# v1.net
KiCad netlist of a schematic drawn in EAGLE
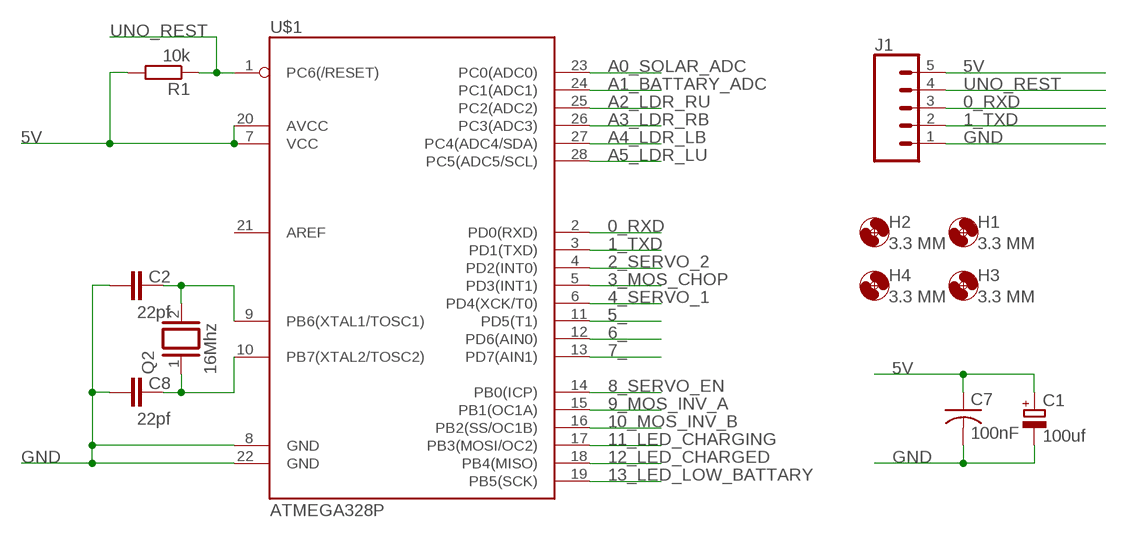
[diagram p0: schematic, sheet 1]
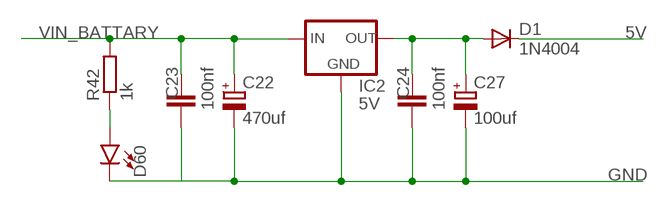
[diagram p1: schematic, sheet 2]
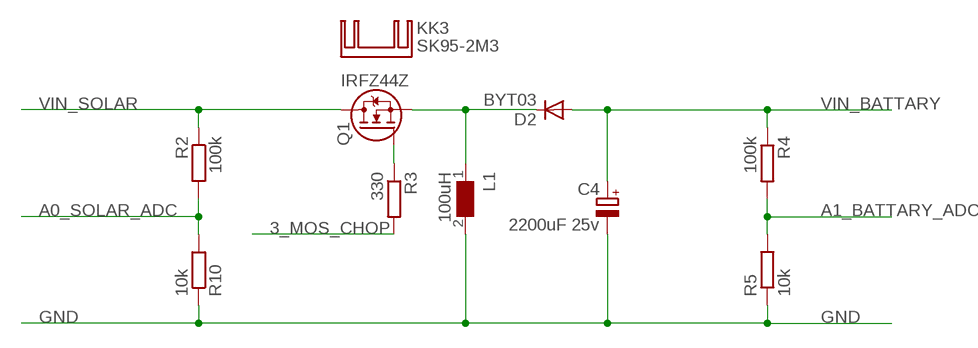
[diagram p2: schematic, sheet 3]
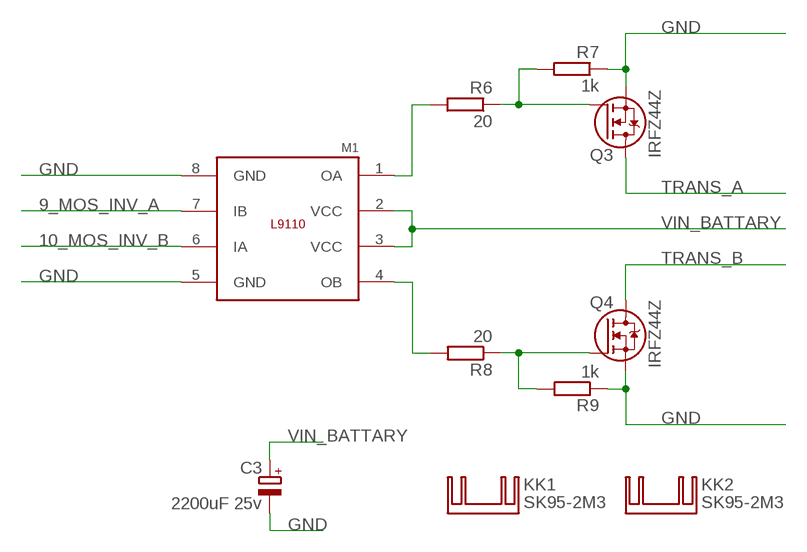
[diagram p3: schematic, sheet 4]
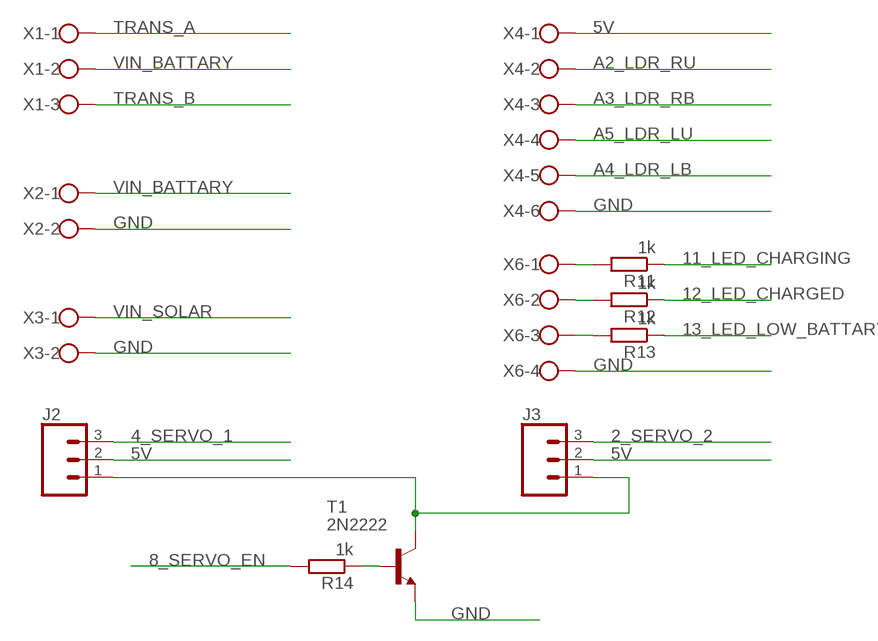
[diagram p4: schematic, sheet 5]

(export (version "E")
  (design (tool "Eeschema 10.0.6"))
  (components
    (comp (ref "C3")
      (value "2200uF 25v")
      (footprint "eagle-import:E5-13")
      (libsource (lib "eagle-import") (part "rcl_334_CPOL-EUE5-13"))
    )
    (comp (ref "KK1")
      (value "SK95-2M3")
      (footprint "eagle-import:SK95-2M3")
      (libsource (lib "eagle-import") (part "SK95-2M3"))
    )
    (comp (ref "KK2")
      (value "SK95-2M3")
      (footprint "eagle-import:SK95-2M3")
      (libsource (lib "eagle-import") (part "SK95-2M3"))
    )
    (comp (ref "M1")
      (value "L9110")
      (footprint "eagle-import:SO8P")
      (libsource (lib "eagle-import") (part "L9110"))
    )
    (comp (ref "Q3")
      (value "IRFZ44Z")
      (footprint "eagle-import:TO220V")
      (libsource (lib "eagle-import") (part "IRFZ44Z"))
    )
    (comp (ref "Q4")
      (value "IRFZ44Z")
      (footprint "eagle-import:TO220V")
      (libsource (lib "eagle-import") (part "IRFZ44Z"))
    )
    (comp (ref "R6")
      (value "20")
      (footprint "eagle-import:0207_10")
      (libsource (lib "eagle-import") (part "R-EU_0207/10"))
    )
    (comp (ref "R7")
      (value "1k")
      (footprint "eagle-import:0207_10")
      (libsource (lib "eagle-import") (part "R-EU_0207/10"))
    )
    (comp (ref "R8")
      (value "20")
      (footprint "eagle-import:0207_10")
      (libsource (lib "eagle-import") (part "R-EU_0207/10"))
    )
    (comp (ref "R9")
      (value "1k")
      (footprint "eagle-import:0207_10")
      (libsource (lib "eagle-import") (part "R-EU_0207/10"))
    )
    (comp (ref "C4")
      (value "2200uF 25v")
      (footprint "eagle-import:E5-13")
      (libsource (lib "eagle-import") (part "rcl_334_CPOL-EUE5-13"))
    )
    (comp (ref "D2")
      (value "BYT03")
      (footprint "eagle-import:DO27-15")
      (libsource (lib "eagle-import") (part "BYT03"))
    )
    (comp (ref "KK3")
      (value "SK95-2M3")
      (footprint "eagle-import:SK95-2M3")
      (libsource (lib "eagle-import") (part "SK95-2M3"))
    )
    (comp (ref "L1")
      (value "100uH")
      (footprint "eagle-import:WE-ZB")
      (libsource (lib "eagle-import") (part "WE-ZB"))
    )
    (comp (ref "Q1")
      (value "IRFZ44Z")
      (footprint "eagle-import:TO220V")
      (libsource (lib "eagle-import") (part "IRFZ44Z"))
    )
    (comp (ref "R2")
      (value "100k")
      (footprint "eagle-import:0207_10")
      (libsource (lib "eagle-import") (part "R-EU_0207/10"))
    )
    (comp (ref "R3")
      (value "330")
      (footprint "eagle-import:0207_10")
      (libsource (lib "eagle-import") (part "R-EU_0207/10"))
    )
    (comp (ref "R4")
      (value "100k")
      (footprint "eagle-import:0207_10")
      (libsource (lib "eagle-import") (part "R-EU_0207/10"))
    )
    (comp (ref "R5")
      (value "10k")
      (footprint "eagle-import:0207_10")
      (libsource (lib "eagle-import") (part "R-EU_0207/10"))
    )
    (comp (ref "R10")
      (value "10k")
      (footprint "eagle-import:0207_10")
      (libsource (lib "eagle-import") (part "R-EU_0207/10"))
    )
    (comp (ref "C22")
      (value "470uf")
      (footprint "eagle-import:E3,5-8")
      (libsource (lib "eagle-import") (part "CPOL-EUE3.5-8"))
    )
    (comp (ref "C23")
      (value "100nf")
      (footprint "eagle-import:C050-030X075")
      (libsource (lib "eagle-import") (part "C-EU050-030X075"))
    )
    (comp (ref "C24")
      (value "100nf")
      (footprint "eagle-import:C050-030X075")
      (libsource (lib "eagle-import") (part "C-EU050-030X075"))
    )
    (comp (ref "C27")
      (value "100uf")
      (footprint "eagle-import:E3,5-8")
      (libsource (lib "eagle-import") (part "CPOL-EUE3.5-8"))
    )
    (comp (ref "D1")
      (value "1N4004")
      (footprint "eagle-import:DO41-10")
      (libsource (lib "eagle-import") (part "1N4004"))
    )
    (comp (ref "D60")
      (value "LED5MM")
      (footprint "eagle-import:LED_5MM")
      (libsource (lib "eagle-import") (part "LED5MM"))
    )
    (comp (ref "IC2")
      (value "5V")
      (footprint "eagle-import:78XXL")
      (libsource (lib "eagle-import") (part "V_REG_78XXSIDE"))
    )
    (comp (ref "R42")
      (value "1k")
      (footprint "eagle-import:0207_10")
      (libsource (lib "eagle-import") (part "R-EU_0207/10"))
    )
    (comp (ref "J2")
      (value "CONN_03JST-PTH-VERT")
      (footprint "eagle-import:JST-3-PTH-VERT")
      (libsource (lib "eagle-import") (part "CONN_03JST-PTH-VERT"))
    )
    (comp (ref "J3")
      (value "CONN_03JST-PTH-VERT")
      (footprint "eagle-import:JST-3-PTH-VERT")
      (libsource (lib "eagle-import") (part "CONN_03JST-PTH-VERT"))
    )
    (comp (ref "R11")
      (value "1k")
      (footprint "eagle-import:0207_10")
      (libsource (lib "eagle-import") (part "R-EU_0207/10"))
    )
    (comp (ref "R12")
      (value "1k")
      (footprint "eagle-import:0207_10")
      (libsource (lib "eagle-import") (part "R-EU_0207/10"))
    )
    (comp (ref "R13")
      (value "1k")
      (footprint "eagle-import:0207_10")
      (libsource (lib "eagle-import") (part "R-EU_0207/10"))
    )
    (comp (ref "R14")
      (value "1k")
      (footprint "eagle-import:0207_10")
      (libsource (lib "eagle-import") (part "R-EU_0207/10"))
    )
    (comp (ref "T1")
      (value "2N2222")
      (footprint "eagle-import:TO92-EBC-OVAL")
      (libsource (lib "eagle-import") (part "2N2222"))
    )
    (comp (ref "X1")
      (value "W237-103")
      (footprint "eagle-import:W237-103")
      (fields (field (name "MPN") "237-103"))
      (libsource (lib "eagle-import") (part "W237-103"))
    )
    (comp (ref "X2")
      (value "W237-102")
      (footprint "eagle-import:W237-102")
      (fields (field (name "MPN") "237-102"))
      (libsource (lib "eagle-import") (part "W237-102"))
    )
    (comp (ref "X3")
      (value "W237-102")
      (footprint "eagle-import:W237-102")
      (fields (field (name "MPN") "237-102"))
      (libsource (lib "eagle-import") (part "W237-102"))
    )
    (comp (ref "X4")
      (value "W237-6")
      (footprint "eagle-import:W237-6")
      (libsource (lib "eagle-import") (part "W237-6"))
    )
    (comp (ref "X6")
      (value "W237-4")
      (footprint "eagle-import:W237-4")
      (libsource (lib "eagle-import") (part "W237-4"))
    )
    (comp (ref "C1")
      (value "100uf")
      (footprint "eagle-import:E3,5-8")
      (libsource (lib "eagle-import") (part "CPOL-EUE3.5-8"))
    )
    (comp (ref "C2")
      (value "22pf")
      (footprint "eagle-import:C050-030X075")
      (libsource (lib "eagle-import") (part "C-EU050-030X075"))
    )
    (comp (ref "C7")
      (value "100nF")
      (footprint "eagle-import:C050-035X075")
      (libsource (lib "eagle-import") (part "C-US050-035X075"))
    )
    (comp (ref "C8")
      (value "22pf")
      (footprint "eagle-import:C050-030X075")
      (libsource (lib "eagle-import") (part "C-EU050-030X075"))
    )
    (comp (ref "H1")
      (value "3.3 MM")
      (footprint "eagle-import:3,3")
      (libsource (lib "eagle-import") (part "MOUNT-HOLE3.3"))
    )
    (comp (ref "H2")
      (value "3.3 MM")
      (footprint "eagle-import:3,3")
      (libsource (lib "eagle-import") (part "MOUNT-HOLE3.3"))
    )
    (comp (ref "H3")
      (value "3.3 MM")
      (footprint "eagle-import:3,3")
      (libsource (lib "eagle-import") (part "MOUNT-HOLE3.3"))
    )
    (comp (ref "H4")
      (value "3.3 MM")
      (footprint "eagle-import:3,3")
      (libsource (lib "eagle-import") (part "MOUNT-HOLE3.3"))
    )
    (comp (ref "J1")
      (value "CONN_05JST-VERT")
      (footprint "eagle-import:JST-5-PTH-VERT")
      (libsource (lib "eagle-import") (part "CONN_05JST-VERT"))
    )
    (comp (ref "Q2")
      (value "16Mhz")
      (footprint "eagle-import:QS")
      (libsource (lib "eagle-import") (part "XTAL/S"))
    )
    (comp (ref "R1")
      (value "10k")
      (footprint "eagle-import:0207_10")
      (libsource (lib "eagle-import") (part "R-EU_0207/10"))
    )
    (comp (ref "U$1")
      (value "ATMEGA328P")
      (footprint "eagle-import:DIL-28-3")
      (libsource (lib "eagle-import") (part "ATMEGA328P_PDIP"))
    )
  )
  (nets
    (net (code "1") (name "0_RXD") (class "Default")
      (node (ref "J1") (pin "3") (pinfunction "3_3") (pintype "passive"))
      (node (ref "U$1") (pin "2") (pinfunction "PD0(RXD)_2") (pintype "bidirectional"))
    )
    (net (code "2") (name "1_TXD") (class "Default")
      (node (ref "J1") (pin "2") (pinfunction "2_2") (pintype "passive"))
      (node (ref "U$1") (pin "3") (pinfunction "PD1(TXD)_3") (pintype "bidirectional"))
    )
    (net (code "3") (name "2_SERVO_2") (class "Default")
      (node (ref "J3") (pin "3") (pinfunction "3_3") (pintype "passive"))
      (node (ref "U$1") (pin "4") (pinfunction "PD2(INT0)_4") (pintype "bidirectional"))
    )
    (net (code "4") (name "3_MOS_CHOP") (class "Default")
      (node (ref "R3") (pin "2") (pinfunction "2_2") (pintype "passive"))
      (node (ref "U$1") (pin "5") (pinfunction "PD3(INT1)_5") (pintype "bidirectional"))
    )
    (net (code "5") (name "4_SERVO_1") (class "Default")
      (node (ref "J2") (pin "3") (pinfunction "3_3") (pintype "passive"))
      (node (ref "U$1") (pin "6") (pinfunction "PD4(XCK/T0)_6") (pintype "bidirectional"))
    )
    (net (code "6") (name "5V") (class "Default")
      (node (ref "C1") (pin "+") (pinfunction "+_+") (pintype "passive"))
      (node (ref "C7") (pin "1") (pinfunction "1_1") (pintype "passive"))
      (node (ref "D1") (pin "C") (pinfunction "C_C") (pintype "passive"))
      (node (ref "J1") (pin "5") (pinfunction "5_5") (pintype "passive"))
      (node (ref "J2") (pin "2") (pinfunction "2_2") (pintype "passive"))
      (node (ref "J3") (pin "2") (pinfunction "2_2") (pintype "passive"))
      (node (ref "R1") (pin "2") (pinfunction "2_2") (pintype "passive"))
      (node (ref "U$1") (pin "20") (pinfunction "AVCC_20") (pintype "bidirectional"))
      (node (ref "U$1") (pin "7") (pinfunction "VCC_7") (pintype "bidirectional"))
      (node (ref "X4") (pin "1") (pinfunction "KL_1") (pintype "passive"))
    )
    (net (code "7") (name "5_") (class "Default")
      (node (ref "U$1") (pin "11") (pinfunction "PD5(T1)_11") (pintype "bidirectional"))
    )
    (net (code "8") (name "6_") (class "Default")
      (node (ref "U$1") (pin "12") (pinfunction "PD6(AIN0)_12") (pintype "bidirectional"))
    )
    (net (code "9") (name "7_") (class "Default")
      (node (ref "U$1") (pin "13") (pinfunction "PD7(AIN1)_13") (pintype "bidirectional"))
    )
    (net (code "10") (name "8_SERVO_EN") (class "Default")
      (node (ref "R14") (pin "2") (pinfunction "2_2") (pintype "passive"))
      (node (ref "U$1") (pin "14") (pinfunction "PB0(ICP)_14") (pintype "bidirectional"))
    )
    (net (code "11") (name "9_MOS_INV_A") (class "Default")
      (node (ref "M1") (pin "7") (pinfunction "IB_7") (pintype "bidirectional"))
      (node (ref "U$1") (pin "15") (pinfunction "PB1(OC1A)_15") (pintype "bidirectional"))
    )
    (net (code "12") (name "10_MOS_INV_B") (class "Default")
      (node (ref "M1") (pin "6") (pinfunction "IA_6") (pintype "bidirectional"))
      (node (ref "U$1") (pin "16") (pinfunction "PB2(SS/OC1B)_16") (pintype "bidirectional"))
    )
    (net (code "13") (name "11_LED_CHARGING") (class "Default")
      (node (ref "R11") (pin "1") (pinfunction "1_1") (pintype "passive"))
      (node (ref "U$1") (pin "17") (pinfunction "PB3(MOSI/OC2)_17") (pintype "bidirectional"))
    )
    (net (code "14") (name "12_LED_CHARGED") (class "Default")
      (node (ref "R12") (pin "1") (pinfunction "1_1") (pintype "passive"))
      (node (ref "U$1") (pin "18") (pinfunction "PB4(MISO)_18") (pintype "bidirectional"))
    )
    (net (code "15") (name "13_LED_LOW_BATTARY") (class "Default")
      (node (ref "R13") (pin "1") (pinfunction "1_1") (pintype "passive"))
      (node (ref "U$1") (pin "19") (pinfunction "PB5(SCK)_19") (pintype "bidirectional"))
    )
    (net (code "16") (name "A0_SOLAR_ADC") (class "Default")
      (node (ref "R10") (pin "2") (pinfunction "2_2") (pintype "passive"))
      (node (ref "R2") (pin "2") (pinfunction "2_2") (pintype "passive"))
      (node (ref "U$1") (pin "23") (pinfunction "PC0(ADC0)_23") (pintype "bidirectional"))
    )
    (net (code "17") (name "A1_BATTARY_ADC") (class "Default")
      (node (ref "R4") (pin "2") (pinfunction "2_2") (pintype "passive"))
      (node (ref "R5") (pin "2") (pinfunction "2_2") (pintype "passive"))
      (node (ref "U$1") (pin "24") (pinfunction "PC1(ADC1)_24") (pintype "bidirectional"))
    )
    (net (code "18") (name "A2_LDR_RU") (class "Default")
      (node (ref "U$1") (pin "25") (pinfunction "PC2(ADC2)_25") (pintype "bidirectional"))
      (node (ref "X4") (pin "2") (pinfunction "KL_2") (pintype "passive"))
    )
    (net (code "19") (name "A3_LDR_RB") (class "Default")
      (node (ref "U$1") (pin "26") (pinfunction "PC3(ADC3)_26") (pintype "bidirectional"))
      (node (ref "X4") (pin "3") (pinfunction "KL_3") (pintype "passive"))
    )
    (net (code "20") (name "A4_LDR_LB") (class "Default")
      (node (ref "U$1") (pin "27") (pinfunction "PC4(ADC4/SDA)_27") (pintype "bidirectional"))
      (node (ref "X4") (pin "5") (pinfunction "KL_5") (pintype "passive"))
    )
    (net (code "21") (name "A5_LDR_LU") (class "Default")
      (node (ref "U$1") (pin "28") (pinfunction "PC5(ADC5/SCL)_28") (pintype "bidirectional"))
      (node (ref "X4") (pin "4") (pinfunction "KL_4") (pintype "passive"))
    )
    (net (code "22") (name "GND") (class "Default")
      (node (ref "C1") (pin "-") (pinfunction "-_-") (pintype "passive"))
      (node (ref "C2") (pin "1") (pinfunction "1_1") (pintype "passive"))
      (node (ref "C22") (pin "-") (pinfunction "-_-") (pintype "passive"))
      (node (ref "C23") (pin "1") (pinfunction "1_1") (pintype "passive"))
      (node (ref "C24") (pin "1") (pinfunction "1_1") (pintype "passive"))
      (node (ref "C27") (pin "-") (pinfunction "-_-") (pintype "passive"))
      (node (ref "C3") (pin "-") (pinfunction "-_-") (pintype "passive"))
      (node (ref "C4") (pin "-") (pinfunction "-_-") (pintype "passive"))
      (node (ref "C7") (pin "2") (pinfunction "2_2") (pintype "passive"))
      (node (ref "C8") (pin "1") (pinfunction "1_1") (pintype "passive"))
      (node (ref "D60") (pin "K") (pinfunction "C_K") (pintype "passive"))
      (node (ref "IC2") (pin "GND") (pinfunction "GND_GND") (pintype "input"))
      (node (ref "J1") (pin "1") (pinfunction "1_1") (pintype "passive"))
      (node (ref "L1") (pin "2") (pinfunction "2_2") (pintype "passive"))
      (node (ref "M1") (pin "5") (pinfunction "GND_5") (pintype "bidirectional"))
      (node (ref "M1") (pin "8") (pinfunction "GND_8") (pintype "bidirectional"))
      (node (ref "Q3") (pin "3") (pinfunction "S_3") (pintype "passive"))
      (node (ref "Q4") (pin "3") (pinfunction "S_3") (pintype "passive"))
      (node (ref "R10") (pin "1") (pinfunction "1_1") (pintype "passive"))
      (node (ref "R5") (pin "1") (pinfunction "1_1") (pintype "passive"))
      (node (ref "R7") (pin "1") (pinfunction "1_1") (pintype "passive"))
      (node (ref "R9") (pin "1") (pinfunction "1_1") (pintype "passive"))
      (node (ref "T1") (pin "E") (pinfunction "E_E") (pintype "passive"))
      (node (ref "U$1") (pin "22") (pinfunction "GND_22") (pintype "bidirectional"))
      (node (ref "U$1") (pin "8") (pinfunction "GND_8") (pintype "bidirectional"))
      (node (ref "X2") (pin "2") (pinfunction "KL_2") (pintype "passive"))
      (node (ref "X3") (pin "2") (pinfunction "KL_2") (pintype "passive"))
      (node (ref "X4") (pin "6") (pinfunction "KL_6") (pintype "passive"))
      (node (ref "X6") (pin "4") (pinfunction "KL_4") (pintype "passive"))
    )
    (net (code "23") (name "Net-(C24-Pad2)") (class "Default")
      (node (ref "C24") (pin "2") (pinfunction "2_2") (pintype "passive"))
      (node (ref "C27") (pin "+") (pinfunction "+_+") (pintype "passive"))
      (node (ref "D1") (pin "A") (pinfunction "A_A") (pintype "passive"))
      (node (ref "IC2") (pin "OUT") (pinfunction "OUT_OUT") (pintype "output"))
    )
    (net (code "24") (name "Net-(D60-PadA)") (class "Default")
      (node (ref "D60") (pin "A") (pinfunction "A_A") (pintype "passive"))
      (node (ref "R42") (pin "1") (pinfunction "1_1") (pintype "passive"))
    )
    (net (code "25") (name "Net-(J2-Pad1)") (class "Default")
      (node (ref "J2") (pin "1") (pinfunction "1_1") (pintype "passive"))
      (node (ref "J3") (pin "1") (pinfunction "1_1") (pintype "passive"))
      (node (ref "T1") (pin "C") (pinfunction "C_C") (pintype "passive"))
    )
    (net (code "26") (name "Net-(M1-OA)") (class "Default")
      (node (ref "M1") (pin "1") (pinfunction "OA_1") (pintype "bidirectional"))
      (node (ref "R6") (pin "2") (pinfunction "2_2") (pintype "passive"))
    )
    (net (code "27") (name "Net-(M1-OB)") (class "Default")
      (node (ref "M1") (pin "4") (pinfunction "OB_4") (pintype "bidirectional"))
      (node (ref "R8") (pin "2") (pinfunction "2_2") (pintype "passive"))
    )
    (net (code "28") (name "Net-(Q1-G)") (class "Default")
      (node (ref "Q1") (pin "1") (pinfunction "G_1") (pintype "passive"))
      (node (ref "R3") (pin "1") (pinfunction "1_1") (pintype "passive"))
    )
    (net (code "29") (name "Net-(Q1-S)") (class "Default")
      (node (ref "D2") (pin "C") (pinfunction "C_C") (pintype "passive"))
      (node (ref "L1") (pin "1") (pinfunction "1_1") (pintype "passive"))
      (node (ref "Q1") (pin "3") (pinfunction "S_3") (pintype "passive"))
    )
    (net (code "30") (name "Net-(Q3-G)") (class "Default")
      (node (ref "Q3") (pin "1") (pinfunction "G_1") (pintype "passive"))
      (node (ref "R6") (pin "1") (pinfunction "1_1") (pintype "passive"))
      (node (ref "R7") (pin "2") (pinfunction "2_2") (pintype "passive"))
    )
    (net (code "31") (name "Net-(Q4-G)") (class "Default")
      (node (ref "Q4") (pin "1") (pinfunction "G_1") (pintype "passive"))
      (node (ref "R8") (pin "1") (pinfunction "1_1") (pintype "passive"))
      (node (ref "R9") (pin "2") (pinfunction "2_2") (pintype "passive"))
    )
    (net (code "32") (name "Net-(R14-Pad1)") (class "Default")
      (node (ref "R14") (pin "1") (pinfunction "1_1") (pintype "passive"))
      (node (ref "T1") (pin "B") (pinfunction "B_B") (pintype "passive"))
    )
    (net (code "33") (name "Net-(U$1-PB6(XTAL1{slash}TOSC1))") (class "Default")
      (node (ref "C2") (pin "2") (pinfunction "2_2") (pintype "passive"))
      (node (ref "Q2") (pin "2") (pinfunction "2_2") (pintype "passive"))
      (node (ref "U$1") (pin "9") (pinfunction "PB6(XTAL1/TOSC1)_9") (pintype "bidirectional"))
    )
    (net (code "34") (name "Net-(U$1-PB7(XTAL2{slash}TOSC2))") (class "Default")
      (node (ref "C8") (pin "2") (pinfunction "2_2") (pintype "passive"))
      (node (ref "Q2") (pin "1") (pinfunction "1_1") (pintype "passive"))
      (node (ref "U$1") (pin "10") (pinfunction "PB7(XTAL2/TOSC2)_10") (pintype "bidirectional"))
    )
    (net (code "35") (name "Net-(X6A-KL)") (class "Default")
      (node (ref "R11") (pin "2") (pinfunction "2_2") (pintype "passive"))
      (node (ref "X6") (pin "1") (pinfunction "KL_1") (pintype "passive"))
    )
    (net (code "36") (name "Net-(X6B-KL)") (class "Default")
      (node (ref "R12") (pin "2") (pinfunction "2_2") (pintype "passive"))
      (node (ref "X6") (pin "2") (pinfunction "KL_2") (pintype "passive"))
    )
    (net (code "37") (name "Net-(X6C-KL)") (class "Default")
      (node (ref "R13") (pin "2") (pinfunction "2_2") (pintype "passive"))
      (node (ref "X6") (pin "3") (pinfunction "KL_3") (pintype "passive"))
    )
    (net (code "38") (name "TRANS_A") (class "Default")
      (node (ref "Q3") (pin "2") (pinfunction "D_2") (pintype "passive"))
      (node (ref "X1") (pin "1") (pinfunction "KL_1") (pintype "passive"))
    )
    (net (code "39") (name "TRANS_B") (class "Default")
      (node (ref "Q4") (pin "2") (pinfunction "D_2") (pintype "passive"))
      (node (ref "X1") (pin "3") (pinfunction "KL_3") (pintype "passive"))
    )
    (net (code "40") (name "UNO_REST") (class "Default")
      (node (ref "J1") (pin "4") (pinfunction "4_4") (pintype "passive"))
      (node (ref "R1") (pin "1") (pinfunction "1_1") (pintype "passive"))
      (node (ref "U$1") (pin "1") (pinfunction "PC6(/RESET)_1") (pintype "bidirectional"))
    )
    (net (code "41") (name "VIN_BATTARY") (class "Default")
      (node (ref "C22") (pin "+") (pinfunction "+_+") (pintype "passive"))
      (node (ref "C23") (pin "2") (pinfunction "2_2") (pintype "passive"))
      (node (ref "C3") (pin "+") (pinfunction "+_+") (pintype "passive"))
      (node (ref "C4") (pin "+") (pinfunction "+_+") (pintype "passive"))
      (node (ref "D2") (pin "A") (pinfunction "A_A") (pintype "passive"))
      (node (ref "IC2") (pin "IN") (pinfunction "IN_IN") (pintype "input"))
      (node (ref "M1") (pin "2") (pinfunction "VCC_2") (pintype "bidirectional"))
      (node (ref "M1") (pin "3") (pinfunction "VCC_3") (pintype "bidirectional"))
      (node (ref "R4") (pin "1") (pinfunction "1_1") (pintype "passive"))
      (node (ref "R42") (pin "2") (pinfunction "2_2") (pintype "passive"))
      (node (ref "X1") (pin "2") (pinfunction "KL_2") (pintype "passive"))
      (node (ref "X2") (pin "1") (pinfunction "KL_1") (pintype "passive"))
    )
    (net (code "42") (name "VIN_SOLAR") (class "Default")
      (node (ref "Q1") (pin "2") (pinfunction "D_2") (pintype "passive"))
      (node (ref "R2") (pin "1") (pinfunction "1_1") (pintype "passive"))
      (node (ref "X3") (pin "1") (pinfunction "KL_1") (pintype "passive"))
    )
    (net (code "43") (name "unconnected-(U$1-AREF-Pad21)") (class "Default")
      (node (ref "U$1") (pin "21") (pinfunction "AREF_21") (pintype "bidirectional"))
    )
  )
)
